# DorothiController.net
KiCad netlist of a schematic drawn in EAGLE
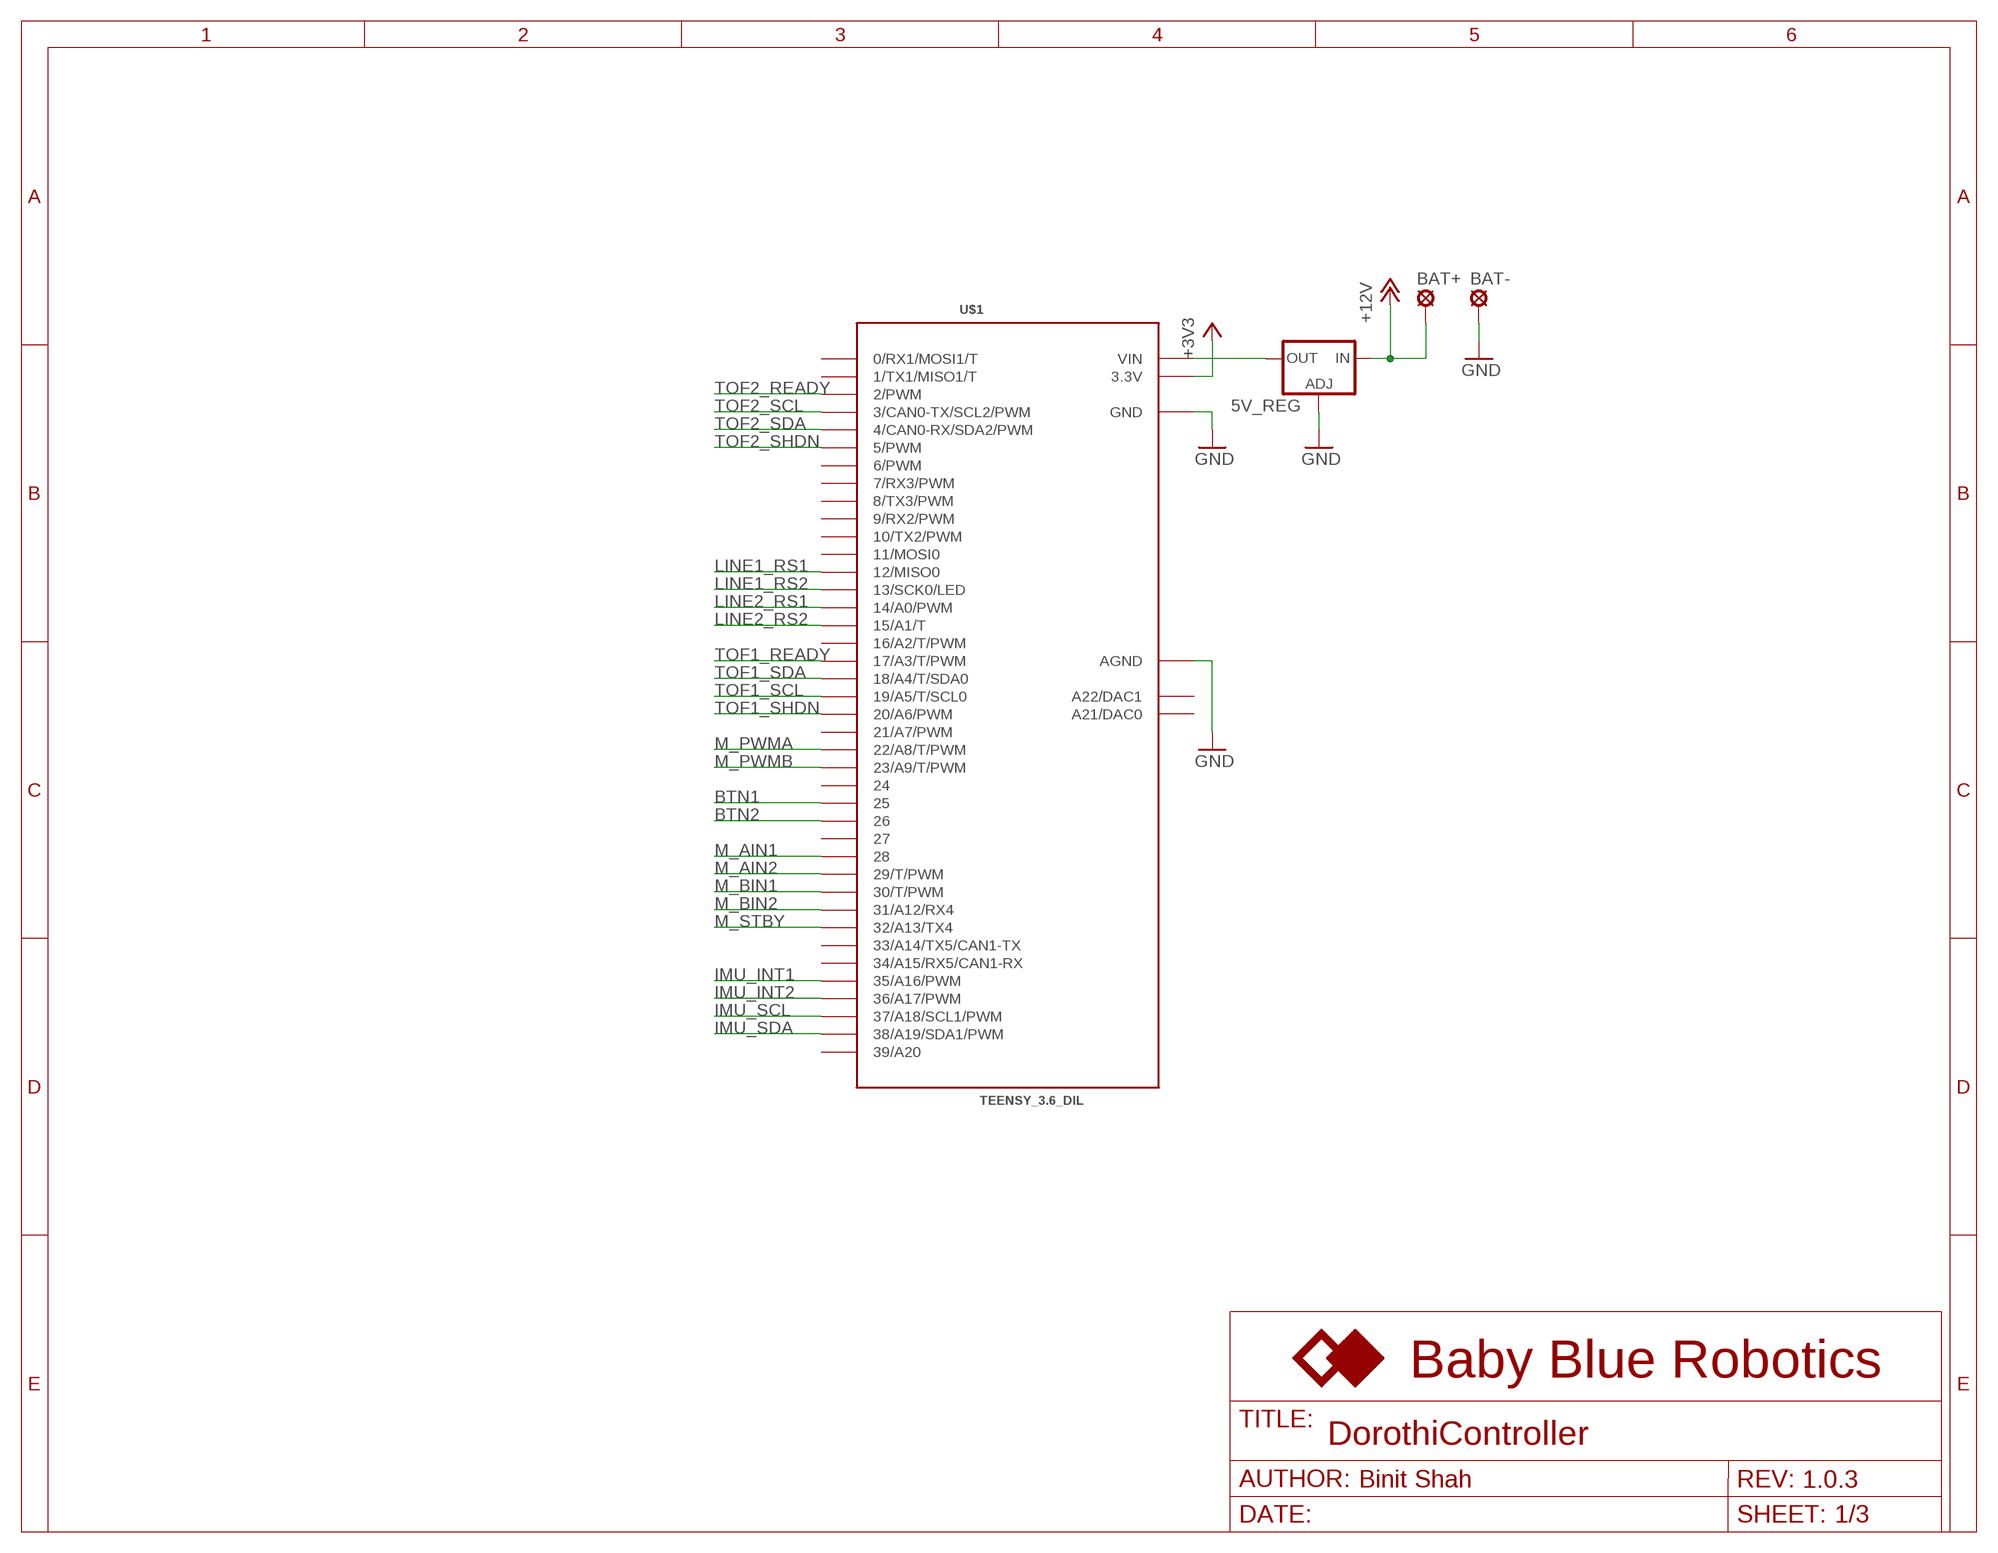
[diagram p0: schematic, sheet 1]
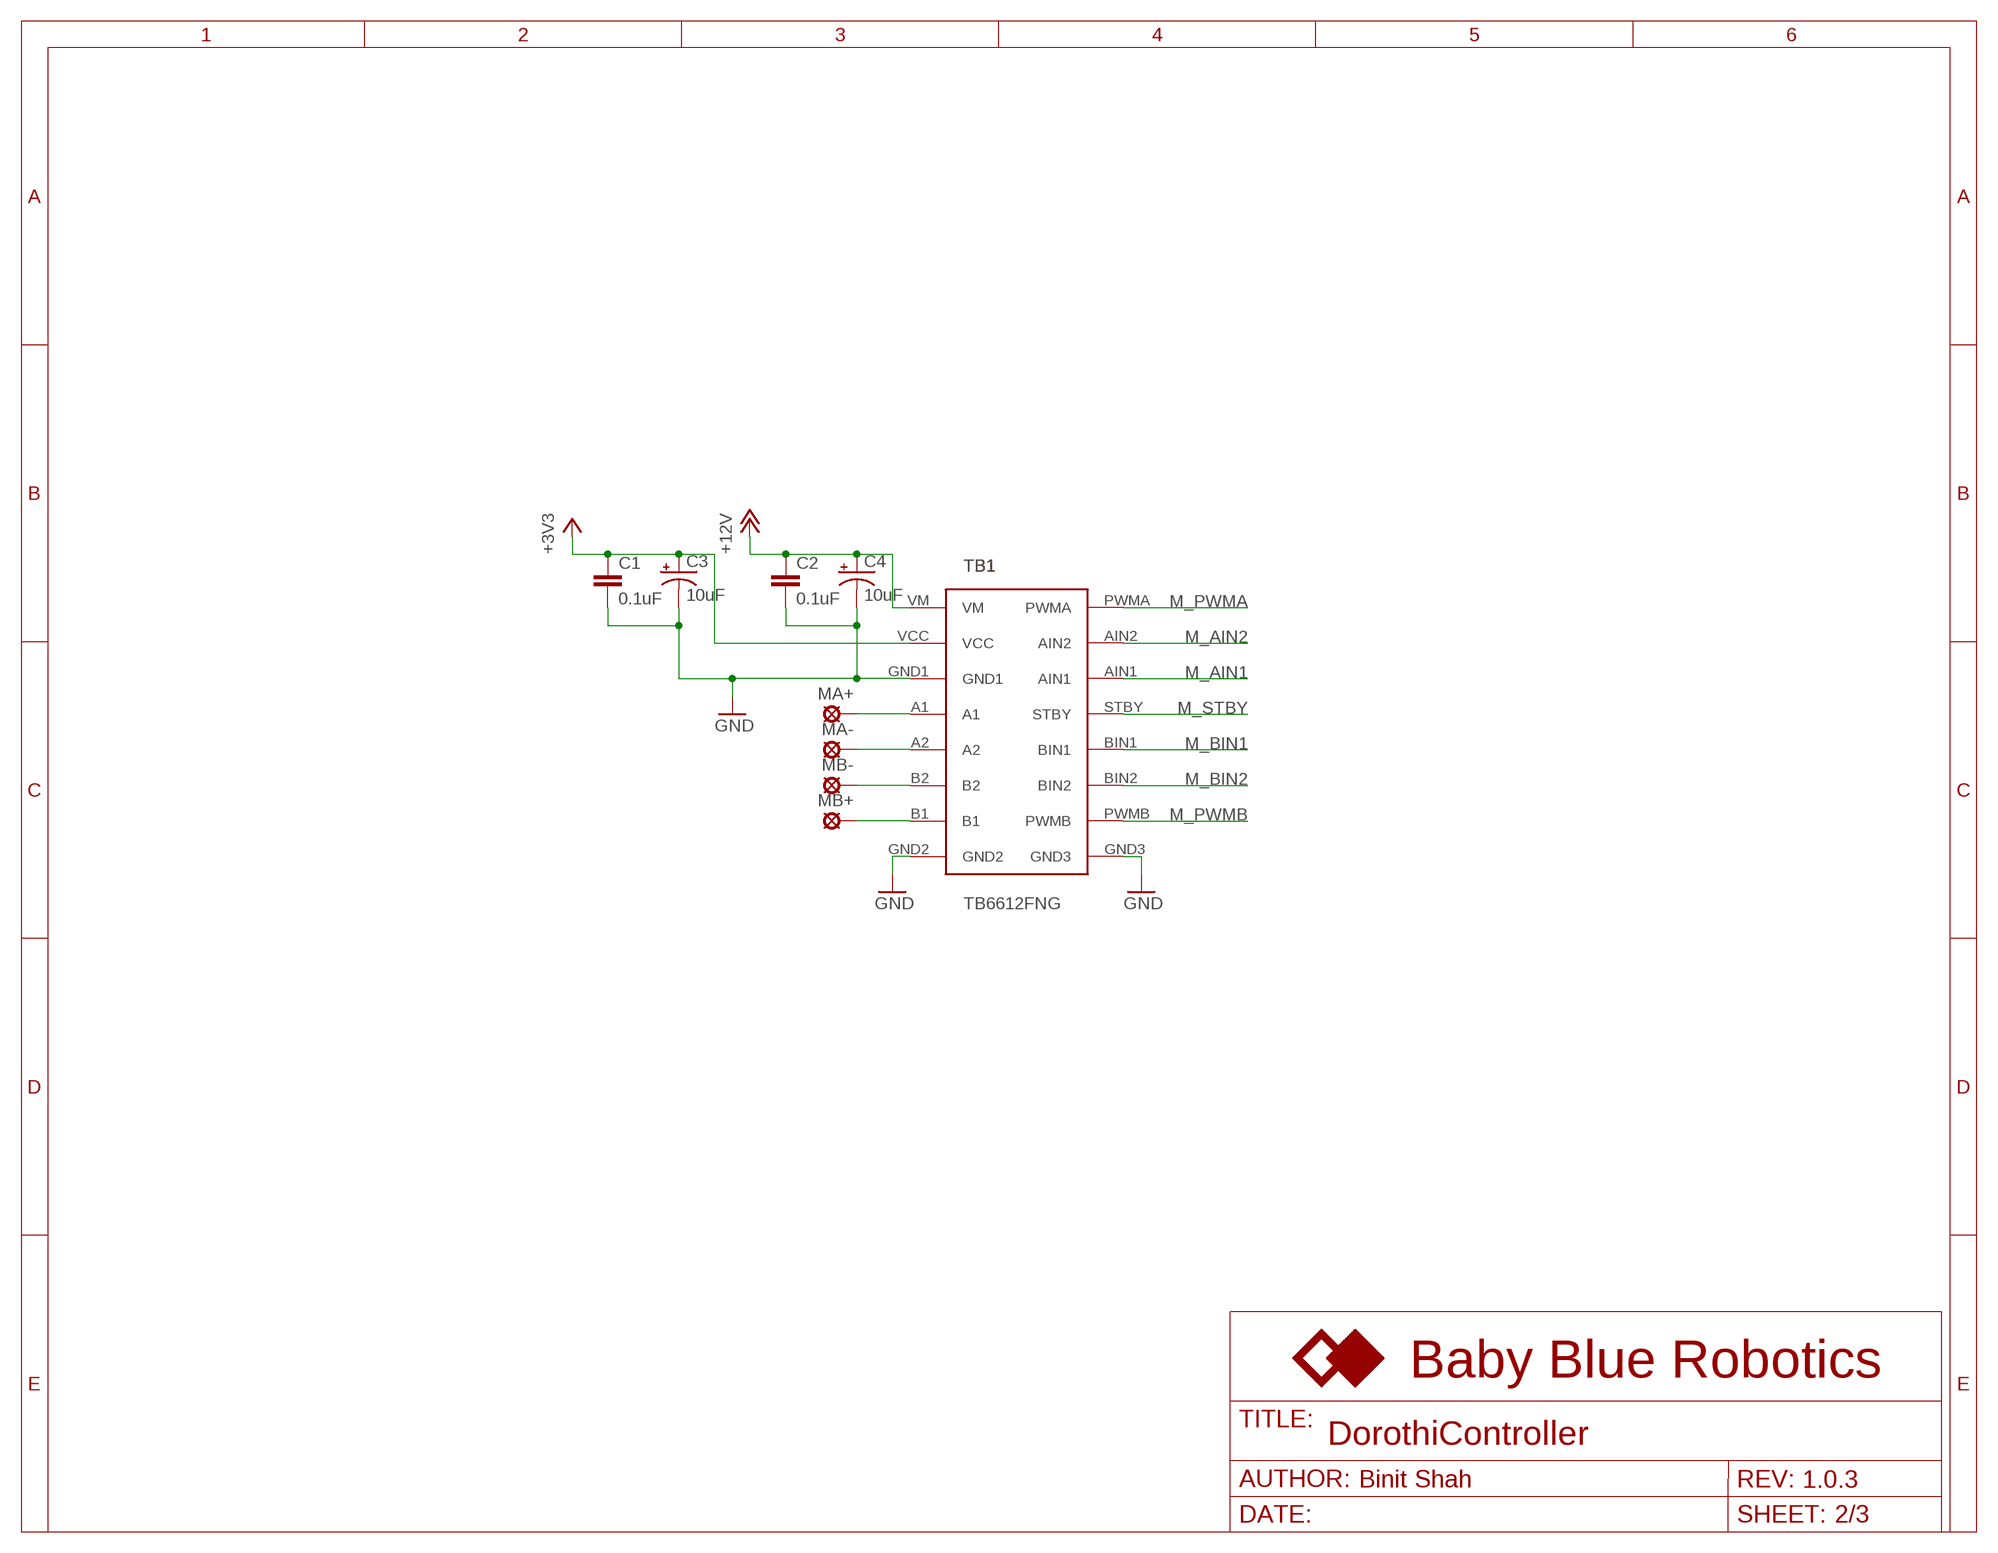
[diagram p1: schematic, sheet 2]
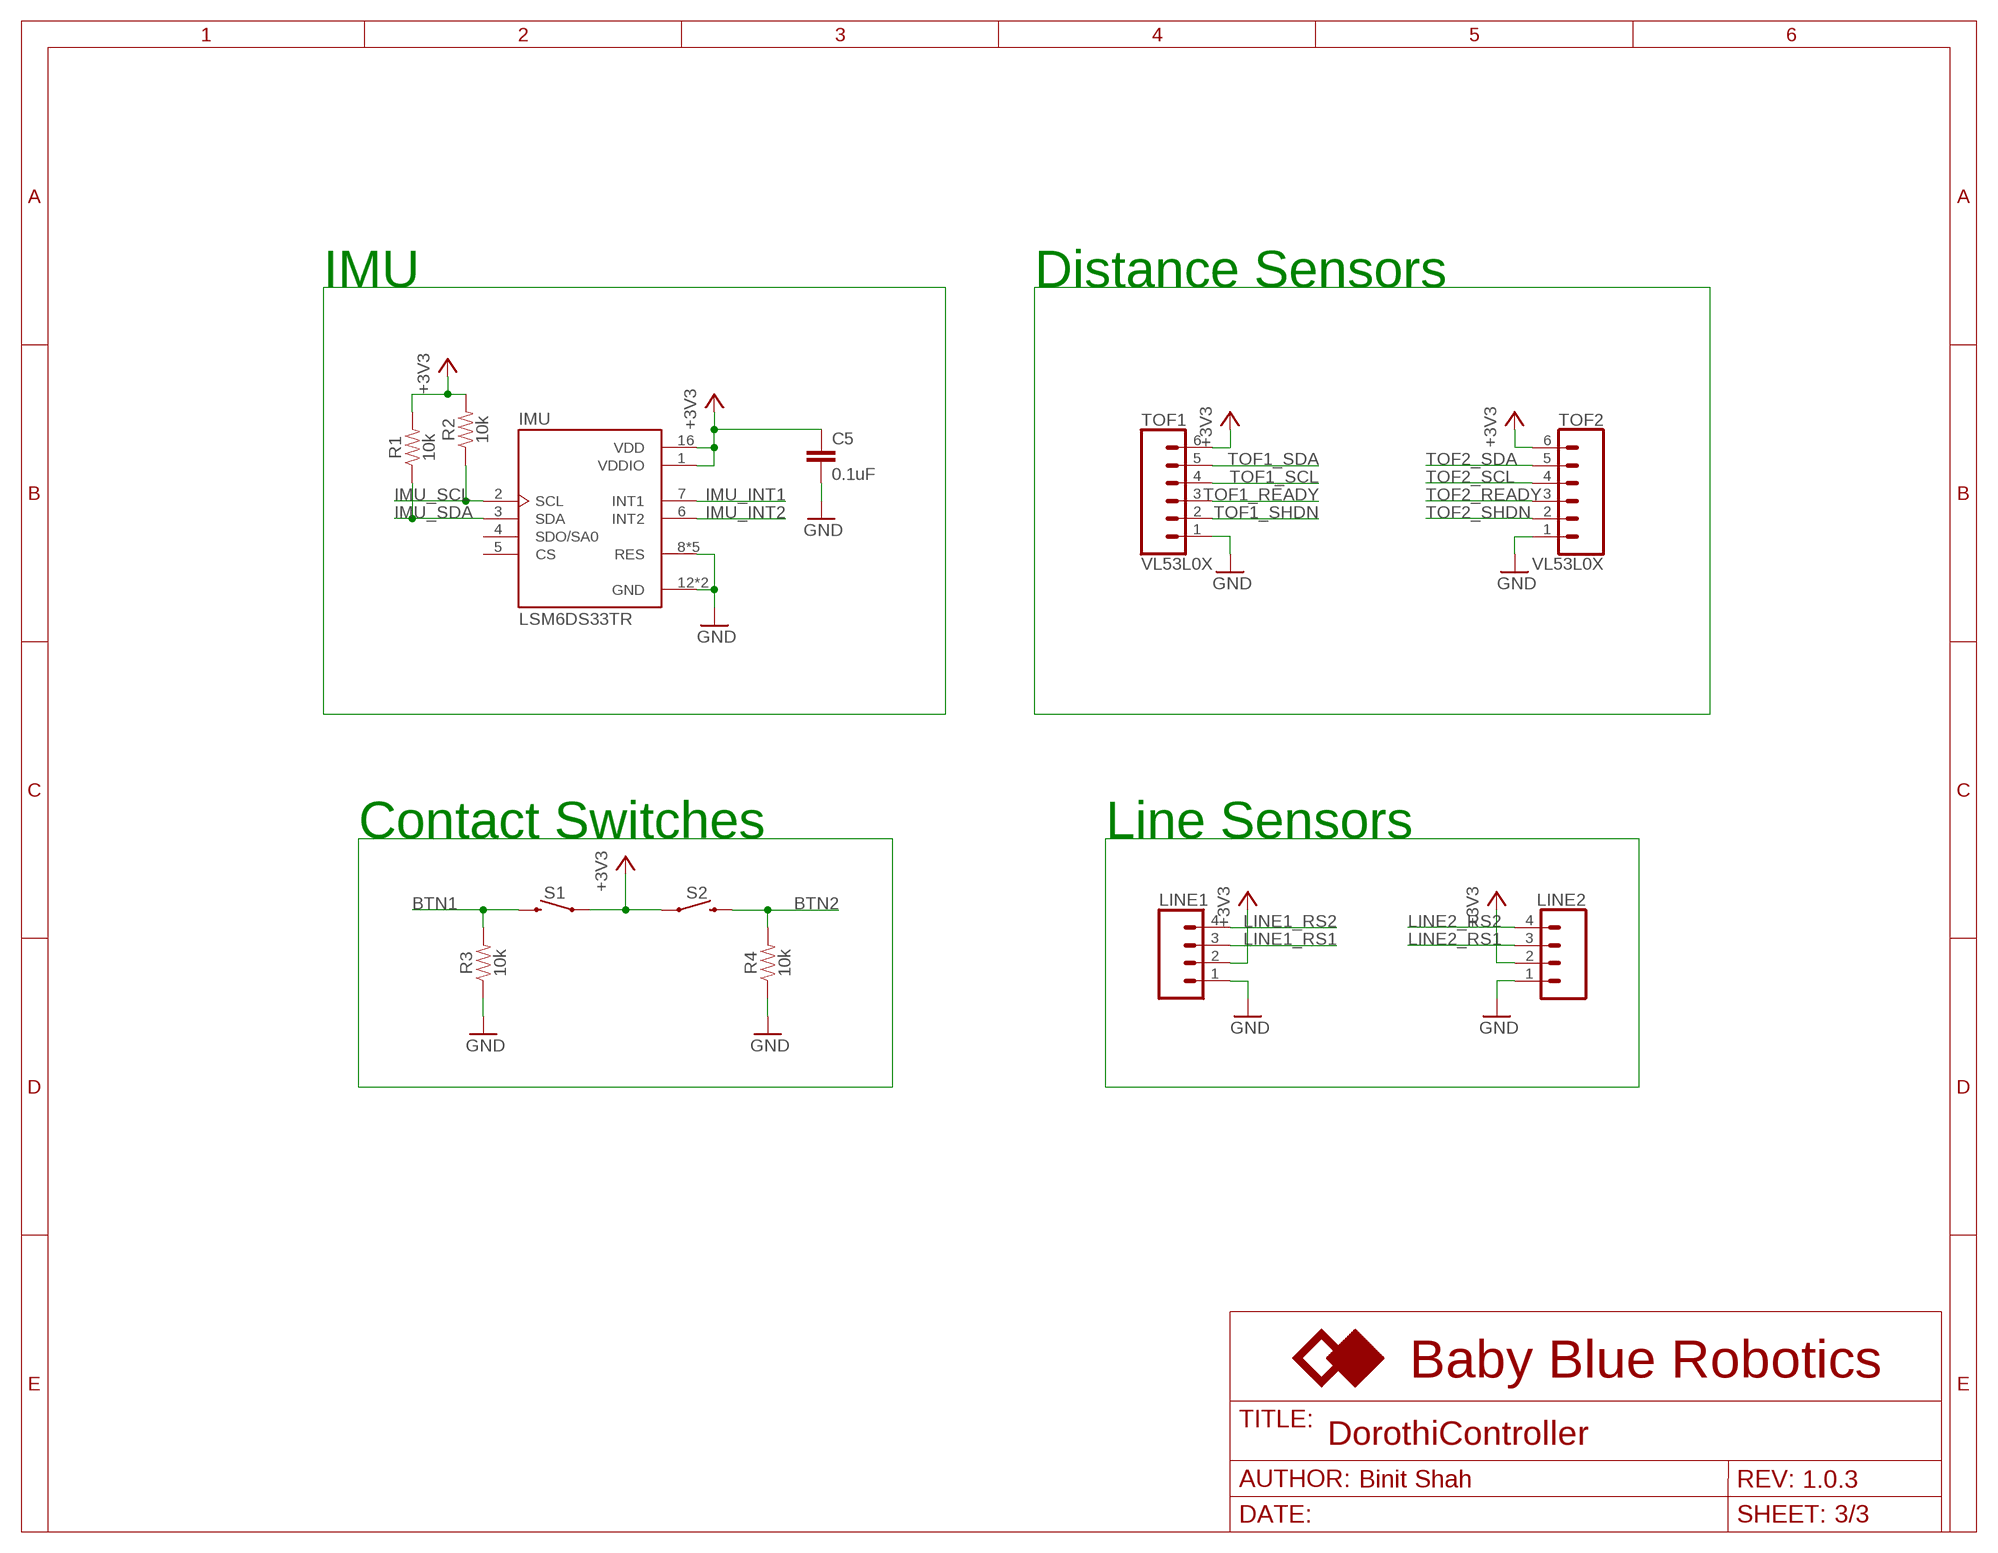
[diagram p2: schematic, sheet 3]

(export (version "E")
  (design (tool "Eeschema 10.0.6"))
  (components
    (comp (ref "C1")
      (value "0.1uF")
      (footprint "eagle-import:0603")
      (libsource (lib "eagle-import") (part "0.1UF-0603-25V-5%"))
    )
    (comp (ref "C2")
      (value "0.1uF")
      (footprint "eagle-import:0603")
      (libsource (lib "eagle-import") (part "0.1UF-0603-25V-5%"))
    )
    (comp (ref "C3")
      (value "10uF")
      (footprint "eagle-import:EIA3528")
      (libsource (lib "eagle-import") (part "10UF-POLAR-EIA3528-20V-10%(TANT)"))
    )
    (comp (ref "C4")
      (value "10uF")
      (footprint "eagle-import:EIA3528")
      (libsource (lib "eagle-import") (part "10UF-POLAR-EIA3528-20V-10%(TANT)"))
    )
    (comp (ref "MA+")
      (value "24_SOLPAD")
      (footprint "eagle-import:WIRE_SOLPAD")
      (libsource (lib "eagle-import") (part "24_SOLPAD"))
    )
    (comp (ref "MA-")
      (value "24_SOLPAD")
      (footprint "eagle-import:WIRE_SOLPAD")
      (libsource (lib "eagle-import") (part "24_SOLPAD"))
    )
    (comp (ref "MB+")
      (value "24_SOLPAD")
      (footprint "eagle-import:WIRE_SOLPAD")
      (libsource (lib "eagle-import") (part "24_SOLPAD"))
    )
    (comp (ref "MB-")
      (value "24_SOLPAD")
      (footprint "eagle-import:WIRE_SOLPAD")
      (libsource (lib "eagle-import") (part "24_SOLPAD"))
    )
    (comp (ref "TB1")
      (value "TB6612FNG")
      (footprint "eagle-import:TB6612FNG")
      (libsource (lib "eagle-import") (part "TB6612FNG"))
    )
    (comp (ref "5V_REG")
      (value "LM138-TL")
      (footprint "eagle-import:TO220L1")
      (libsource (lib "eagle-import") (part "LM138-TL"))
    )
    (comp (ref "BAT+")
      (value "24_SOLPAD")
      (footprint "eagle-import:WIRE_SOLPAD")
      (libsource (lib "eagle-import") (part "24_SOLPAD"))
    )
    (comp (ref "BAT-")
      (value "24_SOLPAD")
      (footprint "eagle-import:WIRE_SOLPAD")
      (libsource (lib "eagle-import") (part "24_SOLPAD"))
    )
    (comp (ref "U$1")
      (value "TEENSY_3.6_DIL")
      (footprint "eagle-import:TEENSY_3.6_DIL")
      (libsource (lib "eagle-import") (part "TEENSY_3.6_DIL"))
    )
    (comp (ref "C5")
      (value "0.1uF")
      (footprint "eagle-import:0603")
      (libsource (lib "eagle-import") (part "0.1UF-0603-25V-5%"))
    )
    (comp (ref "IMU")
      (value "LSM6DS33TR")
      (footprint "eagle-import:PQFN50P300X300X86-16N")
      (fields (field (name "MF") "STMicroelectronics"))
      (libsource (lib "eagle-import") (part "LSM6DS33TR"))
    )
    (comp (ref "LINE1")
      (value "CONN_04")
      (footprint "eagle-import:1X04")
      (libsource (lib "eagle-import") (part "CONN_04"))
    )
    (comp (ref "LINE2")
      (value "CONN_04")
      (footprint "eagle-import:1X04")
      (libsource (lib "eagle-import") (part "CONN_04"))
    )
    (comp (ref "R1")
      (value "10k")
      (footprint "eagle-import:0603")
      (libsource (lib "eagle-import") (part "10KOHM-0603-1/10W-1%"))
    )
    (comp (ref "R2")
      (value "10k")
      (footprint "eagle-import:0603")
      (libsource (lib "eagle-import") (part "10KOHM-0603-1/10W-1%"))
    )
    (comp (ref "R3")
      (value "10k")
      (footprint "eagle-import:0603")
      (libsource (lib "eagle-import") (part "10KOHM-0603-1/10W-1%"))
    )
    (comp (ref "R4")
      (value "10k")
      (footprint "eagle-import:0603")
      (libsource (lib "eagle-import") (part "10KOHM-0603-1/10W-1%"))
    )
    (comp (ref "S1")
      (value "MOMENTARY-SWITCH-SPST-PTH-12MM")
      (footprint "eagle-import:TACTILE_SWITCH_PTH_12MM")
      (libsource (lib "eagle-import") (part "MOMENTARY-SWITCH-SPST-PTH-12MM"))
    )
    (comp (ref "S2")
      (value "MOMENTARY-SWITCH-SPST-PTH-12MM")
      (footprint "eagle-import:TACTILE_SWITCH_PTH_12MM")
      (libsource (lib "eagle-import") (part "MOMENTARY-SWITCH-SPST-PTH-12MM"))
    )
    (comp (ref "TOF1")
      (value "VL53L0X")
      (footprint "eagle-import:1X06")
      (libsource (lib "eagle-import") (part "CONN_06SILK_FEMALE_PTH"))
    )
    (comp (ref "TOF2")
      (value "VL53L0X")
      (footprint "eagle-import:1X06")
      (libsource (lib "eagle-import") (part "CONN_06SILK_FEMALE_PTH"))
    )
  )
  (nets
    (net (code "1") (name "+3V3") (class "Default")
      (node (ref "C1") (pin "1") (pinfunction "1_1") (pintype "passive"))
      (node (ref "C3") (pin "A") (pinfunction "+_A") (pintype "passive"))
      (node (ref "C5") (pin "1") (pinfunction "1_1") (pintype "passive"))
      (node (ref "IMU") (pin "1") (pinfunction "VDDIO_1") (pintype "power_in"))
      (node (ref "IMU") (pin "16") (pinfunction "VDD_16") (pintype "power_in"))
      (node (ref "LINE1") (pin "2") (pinfunction "2_2") (pintype "passive"))
      (node (ref "LINE2") (pin "2") (pinfunction "2_2") (pintype "passive"))
      (node (ref "R1") (pin "2") (pinfunction "2_2") (pintype "passive"))
      (node (ref "R2") (pin "2") (pinfunction "2_2") (pintype "passive"))
      (node (ref "S1") (pin "1") (pinfunction "1_1") (pintype "passive"))
      (node (ref "S2") (pin "1") (pinfunction "1_1") (pintype "passive"))
      (node (ref "TB1") (pin "VCC") (pinfunction "VCC_VCC") (pintype "bidirectional"))
      (node (ref "TOF1") (pin "6") (pinfunction "6_6") (pintype "passive"))
      (node (ref "TOF2") (pin "6") (pinfunction "6_6") (pintype "passive"))
      (node (ref "U$1") (pin "3.3V") (pinfunction "3.3V_3.3V") (pintype "power_in"))
      (node (ref "U$1") (pin "3.3V3") (pinfunction "3.3V_3.3V3") (pintype "power_in"))
    )
    (net (code "2") (name "+12V") (class "Default")
      (node (ref "5V_REG") (pin "3") (pinfunction "IN_3") (pintype "input"))
      (node (ref "BAT+") (pin "P$1") (pinfunction "MP_P$1") (pintype "passive"))
      (node (ref "C2") (pin "1") (pinfunction "1_1") (pintype "passive"))
      (node (ref "C4") (pin "A") (pinfunction "+_A") (pintype "passive"))
      (node (ref "TB1") (pin "VM") (pinfunction "VM_VM") (pintype "bidirectional"))
    )
    (net (code "3") (name "BTN1") (class "Default")
      (node (ref "R3") (pin "2") (pinfunction "2_2") (pintype "passive"))
      (node (ref "S1") (pin "3") (pinfunction "2_3") (pintype "passive"))
      (node (ref "U$1") (pin "25") (pinfunction "25_25") (pintype "bidirectional"))
    )
    (net (code "4") (name "BTN2") (class "Default")
      (node (ref "R4") (pin "2") (pinfunction "2_2") (pintype "passive"))
      (node (ref "S2") (pin "3") (pinfunction "2_3") (pintype "passive"))
      (node (ref "U$1") (pin "26") (pinfunction "26_26") (pintype "bidirectional"))
    )
    (net (code "5") (name "GND") (class "Default")
      (node (ref "5V_REG") (pin "1") (pinfunction "ADJ_1") (pintype "input"))
      (node (ref "BAT-") (pin "P$1") (pinfunction "MP_P$1") (pintype "passive"))
      (node (ref "C1") (pin "2") (pinfunction "2_2") (pintype "passive"))
      (node (ref "C2") (pin "2") (pinfunction "2_2") (pintype "passive"))
      (node (ref "C3") (pin "C") (pinfunction "-_C") (pintype "passive"))
      (node (ref "C4") (pin "C") (pinfunction "-_C") (pintype "passive"))
      (node (ref "C5") (pin "2") (pinfunction "2_2") (pintype "passive"))
      (node (ref "IMU") (pin "10") (pinfunction "RES_10") (pintype "passive"))
      (node (ref "IMU") (pin "11") (pinfunction "RES_11") (pintype "passive"))
      (node (ref "IMU") (pin "12") (pinfunction "GND_12") (pintype "power_in"))
      (node (ref "IMU") (pin "13") (pinfunction "GND_13") (pintype "power_in"))
      (node (ref "IMU") (pin "15") (pinfunction "RES_15") (pintype "passive"))
      (node (ref "IMU") (pin "8") (pinfunction "RES_8") (pintype "passive"))
      (node (ref "IMU") (pin "9") (pinfunction "RES_9") (pintype "passive"))
      (node (ref "LINE1") (pin "1") (pinfunction "1_1") (pintype "passive"))
      (node (ref "LINE2") (pin "1") (pinfunction "1_1") (pintype "passive"))
      (node (ref "R3") (pin "1") (pinfunction "1_1") (pintype "passive"))
      (node (ref "R4") (pin "1") (pinfunction "1_1") (pintype "passive"))
      (node (ref "TB1") (pin "GND1") (pinfunction "GND1_GND1") (pintype "bidirectional"))
      (node (ref "TB1") (pin "GND2") (pinfunction "GND2_GND2") (pintype "bidirectional"))
      (node (ref "TB1") (pin "GND3") (pinfunction "GND3_GND3") (pintype "bidirectional"))
      (node (ref "TOF1") (pin "1") (pinfunction "1_1") (pintype "passive"))
      (node (ref "TOF2") (pin "1") (pinfunction "1_1") (pintype "passive"))
      (node (ref "U$1") (pin "AGND") (pinfunction "AGND_AGND") (pintype "power_in"))
      (node (ref "U$1") (pin "GND") (pinfunction "GND_GND") (pintype "power_in"))
      (node (ref "U$1") (pin "GND1") (pinfunction "GND_GND1") (pintype "power_in"))
    )
    (net (code "6") (name "IMU_INT1") (class "Default")
      (node (ref "IMU") (pin "7") (pinfunction "INT1_7") (pintype "output"))
      (node (ref "U$1") (pin "35/A16") (pinfunction "35/A16/PWM_35/A16") (pintype "bidirectional"))
    )
    (net (code "7") (name "IMU_INT2") (class "Default")
      (node (ref "IMU") (pin "6") (pinfunction "INT2_6") (pintype "output"))
      (node (ref "U$1") (pin "36/A17") (pinfunction "36/A17/PWM_36/A17") (pintype "bidirectional"))
    )
    (net (code "8") (name "IMU_SCL") (class "Default")
      (node (ref "IMU") (pin "2") (pinfunction "SCL_2") (pintype "input"))
      (node (ref "R2") (pin "1") (pinfunction "1_1") (pintype "passive"))
      (node (ref "U$1") (pin "37/A18") (pinfunction "37/A18/SCL1/PWM_37/A18") (pintype "bidirectional"))
    )
    (net (code "9") (name "IMU_SDA") (class "Default")
      (node (ref "IMU") (pin "3") (pinfunction "SDA_3") (pintype "bidirectional"))
      (node (ref "R1") (pin "1") (pinfunction "1_1") (pintype "passive"))
      (node (ref "U$1") (pin "38/A19") (pinfunction "38/A19/SDA1/PWM_38/A19") (pintype "bidirectional"))
    )
    (net (code "10") (name "LINE1_RS1") (class "Default")
      (node (ref "LINE1") (pin "3") (pinfunction "3_3") (pintype "passive"))
      (node (ref "U$1") (pin "12") (pinfunction "12/MISO0_12") (pintype "bidirectional"))
    )
    (net (code "11") (name "LINE1_RS2") (class "Default")
      (node (ref "LINE1") (pin "4") (pinfunction "4_4") (pintype "passive"))
      (node (ref "U$1") (pin "13") (pinfunction "13/SCK0/LED_13") (pintype "bidirectional"))
    )
    (net (code "12") (name "LINE2_RS1") (class "Default")
      (node (ref "LINE2") (pin "3") (pinfunction "3_3") (pintype "passive"))
      (node (ref "U$1") (pin "14/A0") (pinfunction "14/A0/PWM_14/A0") (pintype "bidirectional"))
    )
    (net (code "13") (name "LINE2_RS2") (class "Default")
      (node (ref "LINE2") (pin "4") (pinfunction "4_4") (pintype "passive"))
      (node (ref "U$1") (pin "15/A1") (pinfunction "15/A1/T_15/A1") (pintype "bidirectional"))
    )
    (net (code "14") (name "M_AIN1") (class "Default")
      (node (ref "TB1") (pin "AIN1") (pinfunction "AIN1_AIN1") (pintype "bidirectional"))
      (node (ref "U$1") (pin "28") (pinfunction "28_28") (pintype "bidirectional"))
    )
    (net (code "15") (name "M_AIN2") (class "Default")
      (node (ref "TB1") (pin "AIN2") (pinfunction "AIN2_AIN2") (pintype "bidirectional"))
      (node (ref "U$1") (pin "29") (pinfunction "29/T/PWM_29") (pintype "bidirectional"))
    )
    (net (code "16") (name "M_BIN1") (class "Default")
      (node (ref "TB1") (pin "BIN1") (pinfunction "BIN1_BIN1") (pintype "bidirectional"))
      (node (ref "U$1") (pin "30") (pinfunction "30/T/PWM_30") (pintype "bidirectional"))
    )
    (net (code "17") (name "M_BIN2") (class "Default")
      (node (ref "TB1") (pin "BIN2") (pinfunction "BIN2_BIN2") (pintype "bidirectional"))
      (node (ref "U$1") (pin "31/A12") (pinfunction "31/A12/RX4_31/A12") (pintype "bidirectional"))
    )
    (net (code "18") (name "M_PWMA") (class "Default")
      (node (ref "TB1") (pin "PWMA") (pinfunction "PWMA_PWMA") (pintype "bidirectional"))
      (node (ref "U$1") (pin "22/A8") (pinfunction "22/A8/T/PWM_22/A8") (pintype "bidirectional"))
    )
    (net (code "19") (name "M_PWMB") (class "Default")
      (node (ref "TB1") (pin "PWMB") (pinfunction "PWMB_PWMB") (pintype "bidirectional"))
      (node (ref "U$1") (pin "23/A9") (pinfunction "23/A9/T/PWM_23/A9") (pintype "bidirectional"))
    )
    (net (code "20") (name "M_STBY") (class "Default")
      (node (ref "TB1") (pin "STBY") (pinfunction "STBY_STBY") (pintype "bidirectional"))
      (node (ref "U$1") (pin "32/A13") (pinfunction "32/A13/TX4_32/A13") (pintype "bidirectional"))
    )
    (net (code "21") (name "Net-(5V_REG-OUT)") (class "Default")
      (node (ref "5V_REG") (pin "2") (pinfunction "OUT_2") (pintype "passive"))
      (node (ref "U$1") (pin "VIN") (pinfunction "VIN_VIN") (pintype "power_in"))
    )
    (net (code "22") (name "Net-(MA+-MP)") (class "Default")
      (node (ref "MA+") (pin "P$1") (pinfunction "MP_P$1") (pintype "passive"))
      (node (ref "TB1") (pin "A1") (pinfunction "A1_A1") (pintype "bidirectional"))
    )
    (net (code "23") (name "Net-(MA--MP)") (class "Default")
      (node (ref "MA-") (pin "P$1") (pinfunction "MP_P$1") (pintype "passive"))
      (node (ref "TB1") (pin "A2") (pinfunction "A2_A2") (pintype "bidirectional"))
    )
    (net (code "24") (name "Net-(MB+-MP)") (class "Default")
      (node (ref "MB+") (pin "P$1") (pinfunction "MP_P$1") (pintype "passive"))
      (node (ref "TB1") (pin "B1") (pinfunction "B1_B1") (pintype "bidirectional"))
    )
    (net (code "25") (name "Net-(MB--MP)") (class "Default")
      (node (ref "MB-") (pin "P$1") (pinfunction "MP_P$1") (pintype "passive"))
      (node (ref "TB1") (pin "B2") (pinfunction "B2_B2") (pintype "bidirectional"))
    )
    (net (code "26") (name "TOF1_READY") (class "Default")
      (node (ref "TOF1") (pin "3") (pinfunction "3_3") (pintype "passive"))
      (node (ref "U$1") (pin "17/A3") (pinfunction "17/A3/T/PWM_17/A3") (pintype "bidirectional"))
    )
    (net (code "27") (name "TOF1_SCL") (class "Default")
      (node (ref "TOF1") (pin "4") (pinfunction "4_4") (pintype "passive"))
      (node (ref "U$1") (pin "19/A5") (pinfunction "19/A5/T/SCL0_19/A5") (pintype "bidirectional"))
    )
    (net (code "28") (name "TOF1_SDA") (class "Default")
      (node (ref "TOF1") (pin "5") (pinfunction "5_5") (pintype "passive"))
      (node (ref "U$1") (pin "18/A4") (pinfunction "18/A4/T/SDA0_18/A4") (pintype "bidirectional"))
    )
    (net (code "29") (name "TOF1_SHDN") (class "Default")
      (node (ref "TOF1") (pin "2") (pinfunction "2_2") (pintype "passive"))
      (node (ref "U$1") (pin "20/A6") (pinfunction "20/A6/PWM_20/A6") (pintype "bidirectional"))
    )
    (net (code "30") (name "TOF2_READY") (class "Default")
      (node (ref "TOF2") (pin "3") (pinfunction "3_3") (pintype "passive"))
      (node (ref "U$1") (pin "2") (pinfunction "2/PWM_2") (pintype "bidirectional"))
    )
    (net (code "31") (name "TOF2_SCL") (class "Default")
      (node (ref "TOF2") (pin "4") (pinfunction "4_4") (pintype "passive"))
      (node (ref "U$1") (pin "3") (pinfunction "3/CAN0-TX/SCL2/PWM_3") (pintype "bidirectional"))
    )
    (net (code "32") (name "TOF2_SDA") (class "Default")
      (node (ref "TOF2") (pin "5") (pinfunction "5_5") (pintype "passive"))
      (node (ref "U$1") (pin "4") (pinfunction "4/CAN0-RX/SDA2/PWM_4") (pintype "bidirectional"))
    )
    (net (code "33") (name "TOF2_SHDN") (class "Default")
      (node (ref "TOF2") (pin "2") (pinfunction "2_2") (pintype "passive"))
      (node (ref "U$1") (pin "5") (pinfunction "5/PWM_5") (pintype "bidirectional"))
    )
    (net (code "34") (name "unconnected-(IMU-CS-Pad5)") (class "Default")
      (node (ref "IMU") (pin "5") (pinfunction "CS_5") (pintype "input"))
    )
    (net (code "35") (name "unconnected-(IMU-SDO{slash}SA0-Pad4)") (class "Default")
      (node (ref "IMU") (pin "4") (pinfunction "SDO/SA0_4") (pintype "bidirectional"))
    )
    (net (code "36") (name "unconnected-(U$1-0{slash}RX1{slash}MOSI1{slash}T-Pad0)") (class "Default")
      (node (ref "U$1") (pin "0") (pinfunction "0/RX1/MOSI1/T_0") (pintype "bidirectional"))
    )
    (net (code "37") (name "unconnected-(U$1-1{slash}TX1{slash}MISO1{slash}T-Pad1)") (class "Default")
      (node (ref "U$1") (pin "1") (pinfunction "1/TX1/MISO1/T_1") (pintype "bidirectional"))
    )
    (net (code "38") (name "unconnected-(U$1-6{slash}PWM-Pad6)") (class "Default")
      (node (ref "U$1") (pin "6") (pinfunction "6/PWM_6") (pintype "bidirectional"))
    )
    (net (code "39") (name "unconnected-(U$1-7{slash}RX3{slash}PWM-Pad7)") (class "Default")
      (node (ref "U$1") (pin "7") (pinfunction "7/RX3/PWM_7") (pintype "bidirectional"))
    )
    (net (code "40") (name "unconnected-(U$1-8{slash}TX3{slash}PWM-Pad8)") (class "Default")
      (node (ref "U$1") (pin "8") (pinfunction "8/TX3/PWM_8") (pintype "bidirectional"))
    )
    (net (code "41") (name "unconnected-(U$1-9{slash}RX2{slash}PWM-Pad9)") (class "Default")
      (node (ref "U$1") (pin "9") (pinfunction "9/RX2/PWM_9") (pintype "bidirectional"))
    )
    (net (code "42") (name "unconnected-(U$1-10{slash}TX2{slash}PWM-Pad10)") (class "Default")
      (node (ref "U$1") (pin "10") (pinfunction "10/TX2/PWM_10") (pintype "bidirectional"))
    )
    (net (code "43") (name "unconnected-(U$1-11{slash}MOSI0-Pad11)") (class "Default")
      (node (ref "U$1") (pin "11") (pinfunction "11/MOSI0_11") (pintype "bidirectional"))
    )
    (net (code "44") (name "unconnected-(U$1-16{slash}A2{slash}T{slash}PWM-Pad16{slash}A2)") (class "Default")
      (node (ref "U$1") (pin "16/A2") (pinfunction "16/A2/T/PWM_16/A2") (pintype "bidirectional"))
    )
    (net (code "45") (name "unconnected-(U$1-21{slash}A7{slash}PWM-Pad21{slash}A7)") (class "Default")
      (node (ref "U$1") (pin "21/A7") (pinfunction "21/A7/PWM_21/A7") (pintype "bidirectional"))
    )
    (net (code "46") (name "unconnected-(U$1-33{slash}A14{slash}TX5{slash}CAN1-TX-Pad33{slash}A14)") (class "Default")
      (node (ref "U$1") (pin "33/A14") (pinfunction "33/A14/TX5/CAN1-TX_33/A14") (pintype "bidirectional"))
    )
    (net (code "47") (name "unconnected-(U$1-34{slash}A15{slash}RX5{slash}CAN1-RX-Pad34{slash}A15)") (class "Default")
      (node (ref "U$1") (pin "34/A15") (pinfunction "34/A15/RX5/CAN1-RX_34/A15") (pintype "bidirectional"))
    )
    (net (code "48") (name "unconnected-(U$1-A21{slash}DAC0-PadA21)") (class "Default")
      (node (ref "U$1") (pin "A21") (pinfunction "A21/DAC0_A21") (pintype "bidirectional"))
    )
    (net (code "49") (name "unconnected-(U$1-A22{slash}DAC1-PadA22)") (class "Default")
      (node (ref "U$1") (pin "A22") (pinfunction "A22/DAC1_A22") (pintype "bidirectional"))
    )
    (net (code "50") (name "unconnected-(U$1-Pad24)") (class "Default")
      (node (ref "U$1") (pin "24") (pinfunction "24_24") (pintype "bidirectional"))
    )
    (net (code "51") (name "unconnected-(U$1-Pad27)") (class "Default")
      (node (ref "U$1") (pin "27") (pinfunction "27_27") (pintype "bidirectional"))
    )
    (net (code "52") (name "unconnected-(U$1-Pad39{slash}A20)") (class "Default")
      (node (ref "U$1") (pin "39/A20") (pinfunction "39/A20_39/A20") (pintype "bidirectional"))
    )
  )
)
